# Own_USB-C_Breakout_v2_0_Final.net
KiCad netlist of a schematic drawn in EAGLE
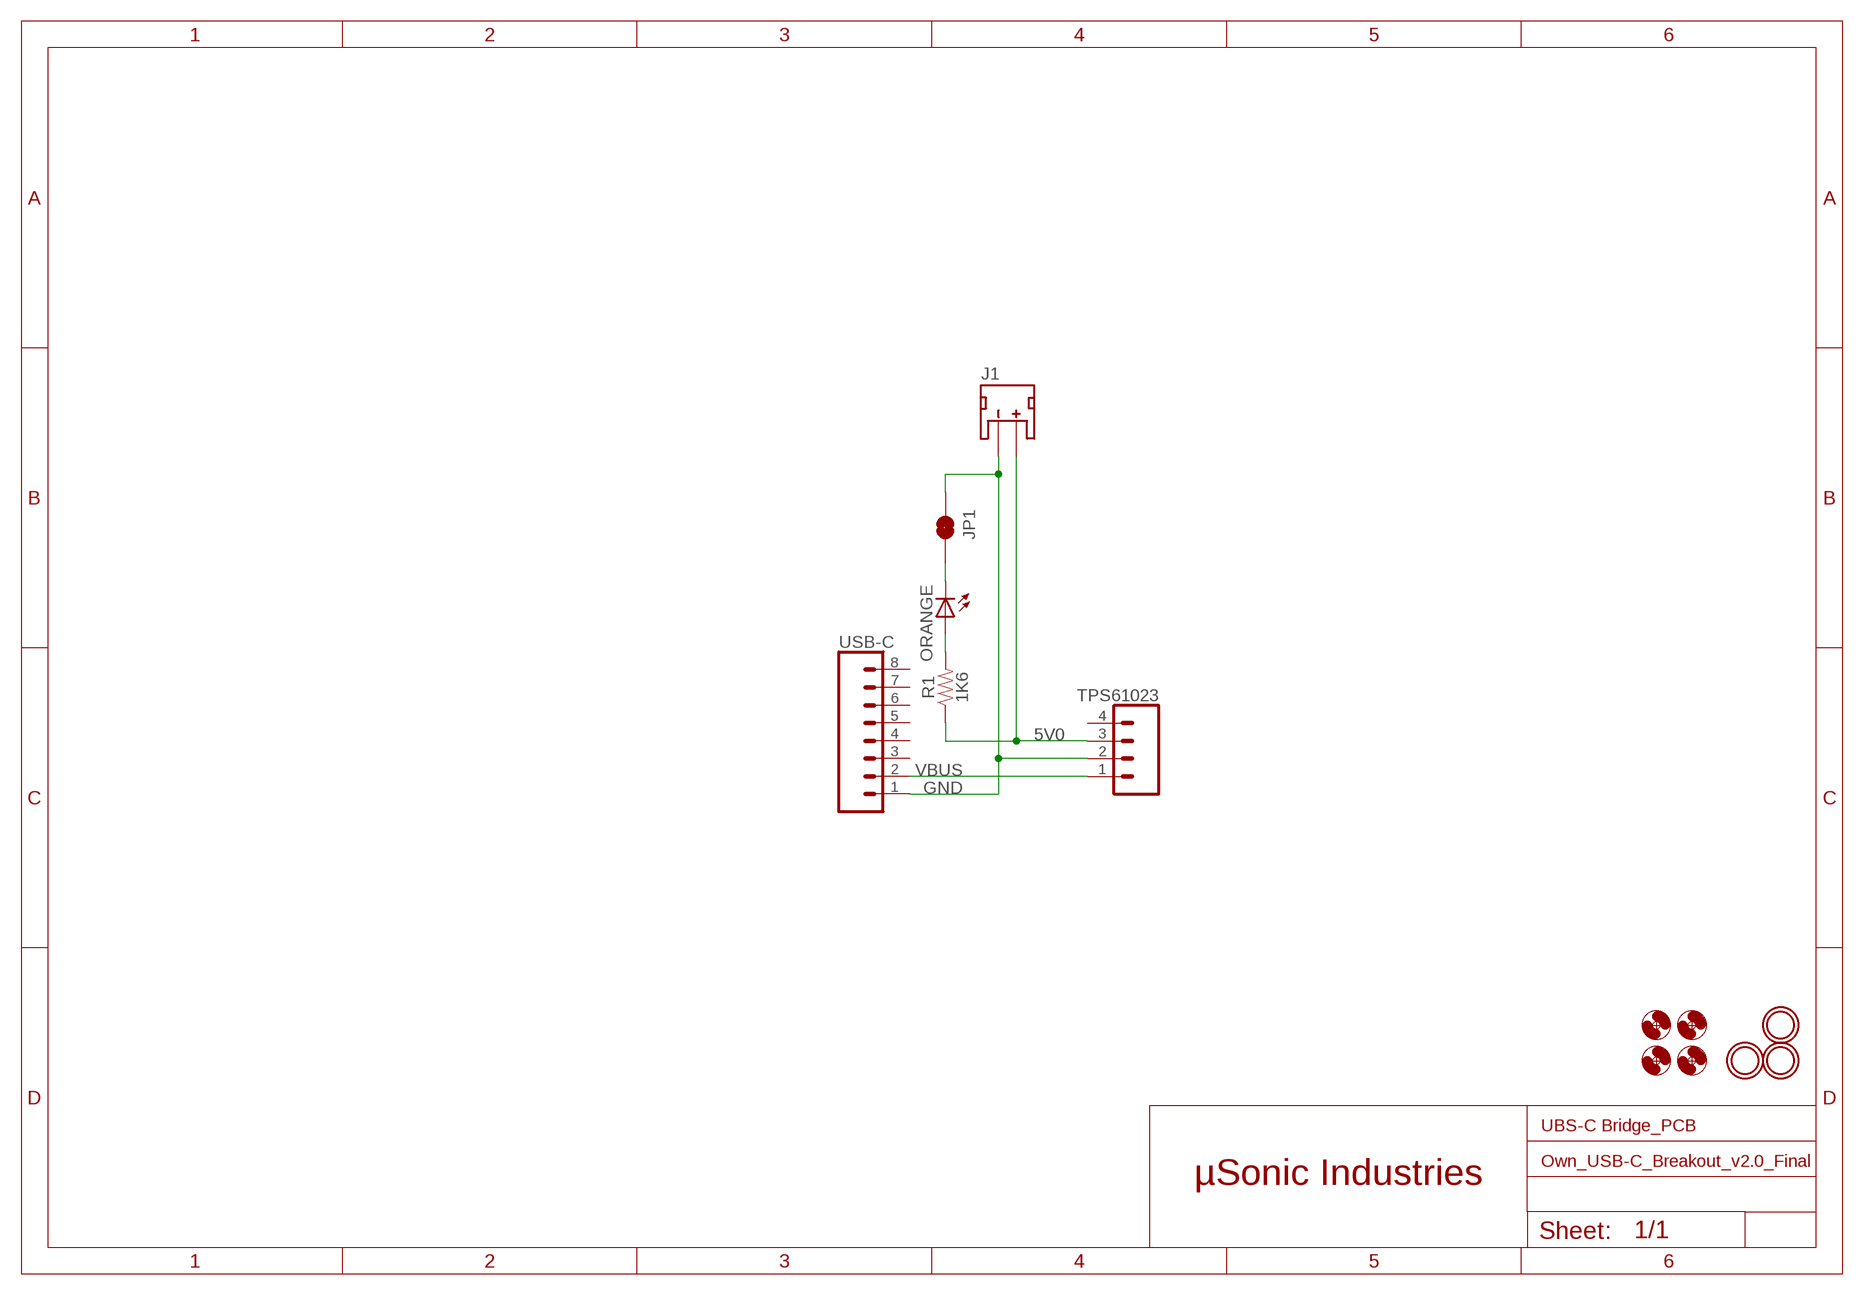
[diagram p0: schematic, sheet 1]

(export (version "E")
  (design (tool "Eeschema 10.0.6"))
  (components
    (comp (ref "J1")
      (value "JST_2MM_MALE")
      (footprint "eagle-import:JST-2-SMD")
      (libsource (lib "eagle-import") (part "JST_2MM_MALE"))
    )
    (comp (ref "JP1")
      (value "JUMPER-SMT_2_NC_TRACE_SILK")
      (footprint "eagle-import:SMT-JUMPER_2_NC_TRACE_SILK")
      (libsource (lib "eagle-import") (part "JUMPER-SMT_2_NC_TRACE_SILK"))
    )
    (comp (ref "ORANGE")
      (value "LEDCHIPLED_0603")
      (footprint "eagle-import:CHIPLED_0603")
      (libsource (lib "eagle-import") (part "LEDCHIPLED_0603"))
    )
    (comp (ref "R1")
      (value "1K6")
      (footprint "eagle-import:0805")
      (libsource (lib "eagle-import") (part "RESISTOR0805"))
    )
    (comp (ref "TPS61023")
      (value "CONN_041X04_NO_SILK")
      (footprint "eagle-import:1X04_NO_SILK")
      (libsource (lib "eagle-import") (part "CONN_041X04_NO_SILK"))
    )
    (comp (ref "U$1")
      (value "MOUNTINGHOLE2.5")
      (footprint "eagle-import:MOUNTINGHOLE_2.5_PLATED")
      (libsource (lib "eagle-import") (part "MOUNTINGHOLE2.5"))
    )
    (comp (ref "U$2")
      (value "MOUNTINGHOLE2.5")
      (footprint "eagle-import:MOUNTINGHOLE_2.5_PLATED")
      (libsource (lib "eagle-import") (part "MOUNTINGHOLE2.5"))
    )
    (comp (ref "U$5")
      (value "MOUNTHOLEBIG")
      (footprint "eagle-import:OWN_MOUNTHOLE_BIGAREA")
      (libsource (lib "eagle-import") (part "MOUNTHOLEBIG"))
    )
    (comp (ref "U$6")
      (value "MOUNTHOLEBIG")
      (footprint "eagle-import:OWN_MOUNTHOLE_BIGAREA")
      (libsource (lib "eagle-import") (part "MOUNTHOLEBIG"))
    )
    (comp (ref "U$7")
      (value "MOUNTHOLEBIG")
      (footprint "eagle-import:OWN_MOUNTHOLE_BIGAREA")
      (libsource (lib "eagle-import") (part "MOUNTHOLEBIG"))
    )
    (comp (ref "U$8")
      (value "MOUNTHOLEBIG")
      (footprint "eagle-import:OWN_MOUNTHOLE_BIGAREA")
      (libsource (lib "eagle-import") (part "MOUNTHOLEBIG"))
    )
    (comp (ref "U$14")
      (value "MOUNTINGHOLE2.5")
      (footprint "eagle-import:MOUNTINGHOLE_2.5_PLATED")
      (libsource (lib "eagle-import") (part "MOUNTINGHOLE2.5"))
    )
    (comp (ref "USB-C")
      (value "CONN_08NO_SILK_FEMALE_PTH")
      (footprint "eagle-import:1X08_NO_SILK")
      (libsource (lib "eagle-import") (part "CONN_08NO_SILK_FEMALE_PTH"))
    )
  )
  (nets
    (net (code "1") (name "/5V0") (class "Default")
      (node (ref "J1") (pin "2") (pinfunction "+_2") (pintype "bidirectional"))
      (node (ref "R1") (pin "1") (pinfunction "1_1") (pintype "passive"))
      (node (ref "TPS61023") (pin "3") (pinfunction "3_3") (pintype "passive"))
    )
    (net (code "2") (name "/GND") (class "Default")
      (node (ref "J1") (pin "1") (pinfunction "-_1") (pintype "bidirectional"))
      (node (ref "JP1") (pin "1") (pinfunction "1_1") (pintype "passive"))
      (node (ref "TPS61023") (pin "2") (pinfunction "2_2") (pintype "passive"))
      (node (ref "USB-C") (pin "1") (pinfunction "1_1") (pintype "passive"))
    )
    (net (code "3") (name "/VBUS") (class "Default")
      (node (ref "TPS61023") (pin "1") (pinfunction "1_1") (pintype "passive"))
      (node (ref "USB-C") (pin "2") (pinfunction "2_2") (pintype "passive"))
    )
    (net (code "4") (name "Net-(JP1-Pad2)") (class "Default")
      (node (ref "JP1") (pin "2") (pinfunction "2_2") (pintype "passive"))
      (node (ref "ORANGE") (pin "C") (pinfunction "C_C") (pintype "passive"))
    )
    (net (code "5") (name "Net-(ORANGE-PadA)") (class "Default")
      (node (ref "ORANGE") (pin "A") (pinfunction "A_A") (pintype "passive"))
      (node (ref "R1") (pin "2") (pinfunction "2_2") (pintype "passive"))
    )
    (net (code "6") (name "unconnected-(J1-PAD1-PadNC1)") (class "Default")
      (node (ref "J1") (pin "NC1") (pinfunction "PAD1_NC1") (pintype "bidirectional"))
    )
    (net (code "7") (name "unconnected-(J1-PAD2-PadNC2)") (class "Default")
      (node (ref "J1") (pin "NC2") (pinfunction "PAD2_NC2") (pintype "bidirectional"))
    )
    (net (code "8") (name "unconnected-(TPS61023-Pad4)") (class "Default")
      (node (ref "TPS61023") (pin "4") (pinfunction "4_4") (pintype "passive"))
    )
    (net (code "9") (name "unconnected-(USB-C-Pad3)") (class "Default")
      (node (ref "USB-C") (pin "3") (pinfunction "3_3") (pintype "passive"))
    )
    (net (code "10") (name "unconnected-(USB-C-Pad4)") (class "Default")
      (node (ref "USB-C") (pin "4") (pinfunction "4_4") (pintype "passive"))
    )
    (net (code "11") (name "unconnected-(USB-C-Pad5)") (class "Default")
      (node (ref "USB-C") (pin "5") (pinfunction "5_5") (pintype "passive"))
    )
    (net (code "12") (name "unconnected-(USB-C-Pad6)") (class "Default")
      (node (ref "USB-C") (pin "6") (pinfunction "6_6") (pintype "passive"))
    )
    (net (code "13") (name "unconnected-(USB-C-Pad7)") (class "Default")
      (node (ref "USB-C") (pin "7") (pinfunction "7_7") (pintype "passive"))
    )
    (net (code "14") (name "unconnected-(USB-C-Pad8)") (class "Default")
      (node (ref "USB-C") (pin "8") (pinfunction "8_8") (pintype "passive"))
    )
  )
)
